# GS_V2.net
KiCad netlist of a schematic drawn in Altium Designer
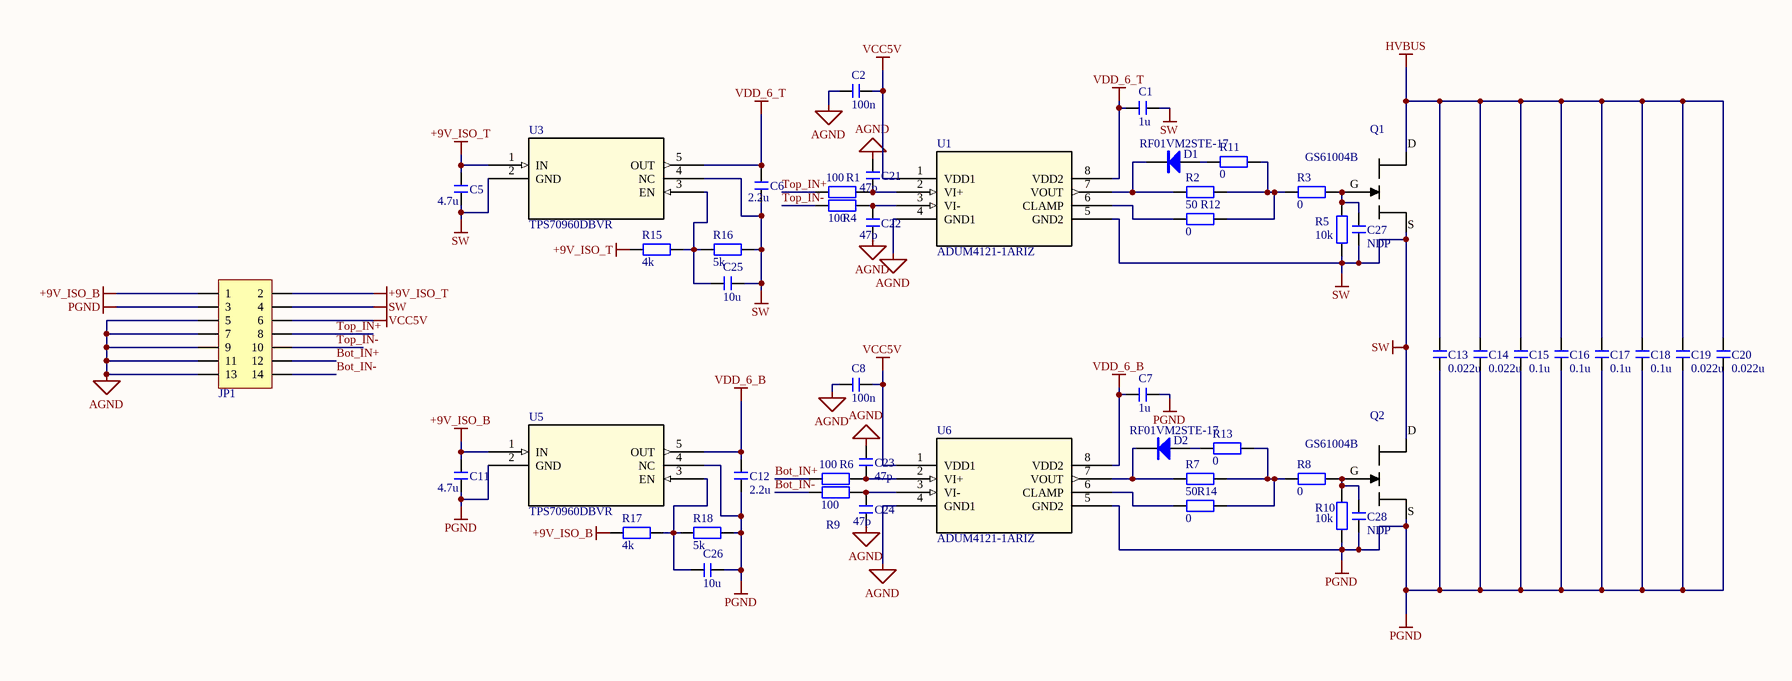
[diagram p0: GS_V2.SchDoc]

(export (version "E")
  (design (tool "Eeschema 10.0.6"))
  (components
    (comp (ref "C1")
      (value "1u")
      (footprint "C 0603_L")
      (description "无极性贴片电容")
      (fields (field (name "版权归属") "源创客"))
      (libsource (lib "3.1   - 电阻-电容-电感") (part "C"))
    )
    (comp (ref "C2")
      (value "100n")
      (footprint "C 0603_L")
      (description "无极性贴片电容")
      (fields (field (name "版权归属") "源创客"))
      (libsource (lib "3.1   - 电阻-电容-电感") (part "C"))
    )
    (comp (ref "C5")
      (value "4.7u")
      (footprint "C 0603_L")
      (description "无极性贴片电容")
      (fields (field (name "版权归属") "源创客"))
      (libsource (lib "3.1   - 电阻-电容-电感") (part "C"))
    )
    (comp (ref "C6")
      (value "2.2u")
      (footprint "C 0603_L")
      (description "无极性贴片电容")
      (fields (field (name "版权归属") "源创客"))
      (libsource (lib "3.1   - 电阻-电容-电感") (part "C"))
    )
    (comp (ref "C7")
      (value "1u")
      (footprint "C 0603_L")
      (description "无极性贴片电容")
      (fields (field (name "版权归属") "源创客"))
      (libsource (lib "3.1   - 电阻-电容-电感") (part "C"))
    )
    (comp (ref "C8")
      (value "100n")
      (footprint "C 0603_L")
      (description "无极性贴片电容")
      (fields (field (name "版权归属") "源创客"))
      (libsource (lib "3.1   - 电阻-电容-电感") (part "C"))
    )
    (comp (ref "C11")
      (value "4.7u")
      (footprint "C 0603_L")
      (description "无极性贴片电容")
      (fields (field (name "版权归属") "源创客"))
      (libsource (lib "3.1   - 电阻-电容-电感") (part "C"))
    )
    (comp (ref "C12")
      (value "2.2u")
      (footprint "C 0603_L")
      (description "无极性贴片电容")
      (fields (field (name "版权归属") "源创客"))
      (libsource (lib "3.1   - 电阻-电容-电感") (part "C"))
    )
    (comp (ref "C13")
      (value "0.022u")
      (footprint "C 0805_L")
      (description "无极性贴片电容")
      (fields (field (name "版权归属") "源创客"))
      (libsource (lib "3.1   - 电阻-电容-电感") (part "C"))
    )
    (comp (ref "C14")
      (value "0.022u")
      (footprint "C 0805_L")
      (description "无极性贴片电容")
      (fields (field (name "版权归属") "源创客"))
      (libsource (lib "3.1   - 电阻-电容-电感") (part "C"))
    )
    (comp (ref "C15")
      (value "0.1u")
      (footprint "C 0805_L")
      (description "无极性贴片电容")
      (fields (field (name "版权归属") "源创客"))
      (libsource (lib "3.1   - 电阻-电容-电感") (part "C"))
    )
    (comp (ref "C16")
      (value "0.1u")
      (footprint "C 0805_L")
      (description "无极性贴片电容")
      (fields (field (name "版权归属") "源创客"))
      (libsource (lib "3.1   - 电阻-电容-电感") (part "C"))
    )
    (comp (ref "C17")
      (value "0.1u")
      (footprint "C 0805_L")
      (description "无极性贴片电容")
      (fields (field (name "版权归属") "源创客"))
      (libsource (lib "3.1   - 电阻-电容-电感") (part "C"))
    )
    (comp (ref "C18")
      (value "0.1u")
      (footprint "C 0805_L")
      (description "无极性贴片电容")
      (fields (field (name "版权归属") "源创客"))
      (libsource (lib "3.1   - 电阻-电容-电感") (part "C"))
    )
    (comp (ref "C19")
      (value "0.022u")
      (footprint "C 0805_L")
      (description "无极性贴片电容")
      (fields (field (name "版权归属") "源创客"))
      (libsource (lib "3.1   - 电阻-电容-电感") (part "C"))
    )
    (comp (ref "C20")
      (value "0.022u")
      (footprint "C 0805_L")
      (description "无极性贴片电容")
      (fields (field (name "版权归属") "源创客"))
      (libsource (lib "3.1   - 电阻-电容-电感") (part "C"))
    )
    (comp (ref "C21")
      (value "47p")
      (footprint "C 0603_L")
      (description "无极性贴片电容")
      (fields (field (name "版权归属") "源创客"))
      (libsource (lib "3.1   - 电阻-电容-电感") (part "C"))
    )
    (comp (ref "C22")
      (value "47p")
      (footprint "C 0603_L")
      (description "无极性贴片电容")
      (fields (field (name "版权归属") "源创客"))
      (libsource (lib "3.1   - 电阻-电容-电感") (part "C"))
    )
    (comp (ref "C23")
      (value "47p")
      (footprint "C 0603_L")
      (description "无极性贴片电容")
      (fields (field (name "版权归属") "源创客"))
      (libsource (lib "3.1   - 电阻-电容-电感") (part "C"))
    )
    (comp (ref "C24")
      (value "47p")
      (footprint "C 0603_L")
      (description "无极性贴片电容")
      (fields (field (name "版权归属") "源创客"))
      (libsource (lib "3.1   - 电阻-电容-电感") (part "C"))
    )
    (comp (ref "C25")
      (value "10u")
      (footprint "C 0603_L")
      (description "无极性贴片电容")
      (fields (field (name "版权归属") "源创客"))
      (libsource (lib "3.1   - 电阻-电容-电感") (part "C"))
    )
    (comp (ref "C26")
      (value "10u")
      (footprint "C 0603_L")
      (description "无极性贴片电容")
      (fields (field (name "版权归属") "源创客"))
      (libsource (lib "3.1   - 电阻-电容-电感") (part "C"))
    )
    (comp (ref "C27")
      (value "NDP")
      (footprint "C 0603_L")
      (description "无极性贴片电容")
      (fields (field (name "版权归属") "源创客"))
      (libsource (lib "3.1   - 电阻-电容-电感") (part "C"))
    )
    (comp (ref "C28")
      (value "NDP")
      (footprint "C 0603_L")
      (description "无极性贴片电容")
      (fields (field (name "版权归属") "源创客"))
      (libsource (lib "3.1   - 电阻-电容-电感") (part "C"))
    )
    (comp (ref "D1")
      (value "RF01VM2STE-17")
      (footprint "SOD-323")
      (description "肖特基二极管")
      (fields (field (name "版权归属") "源创客"))
      (libsource (lib "8.1   - 二极管-整流桥") (part "1N5819"))
    )
    (comp (ref "D2")
      (value "RF01VM2STE-17")
      (footprint "SOD-323")
      (description "肖特基二极管")
      (fields (field (name "版权归属") "源创客"))
      (libsource (lib "8.1   - 二极管-整流桥") (part "1N5819"))
    )
    (comp (ref "JP1")
      (value "Header 2X7")
      (footprint "HDR2.54-WI-2x7P")
      (description "7*2P接插件")
      (fields (field (name "版权归属") "源创客"))
      (libsource (lib "4.6   - 接插件-脚距2.54") (part "Header 7X2"))
    )
    (comp (ref "Q1")
      (value "GS61004B")
      (footprint "GS61004B")
      (description "GAN TRANS E-MODE 100V")
      (libsource (lib "GANSYS_ALTIUM_SYMBOL_20220525") (part "GS61004B"))
    )
    (comp (ref "Q2")
      (value "GS61004B")
      (footprint "GS61004B")
      (description "GAN TRANS E-MODE 100V")
      (libsource (lib "GANSYS_ALTIUM_SYMBOL_20220525") (part "GS61004B"))
    )
    (comp (ref "R1")
      (value "100")
      (footprint "R 0603_L")
      (description "贴片电阻")
      (fields (field (name "版权归属") "源创客"))
      (libsource (lib "3.1   - 电阻-电容-电感") (part "R"))
    )
    (comp (ref "R2")
      (value "50")
      (footprint "R 0603_L")
      (description "贴片电阻")
      (fields (field (name "版权归属") "源创客"))
      (libsource (lib "3.1   - 电阻-电容-电感") (part "R"))
    )
    (comp (ref "R3")
      (value "0")
      (footprint "R 0603_L")
      (description "贴片电阻")
      (fields (field (name "版权归属") "源创客"))
      (libsource (lib "3.1   - 电阻-电容-电感") (part "R"))
    )
    (comp (ref "R4")
      (value "100")
      (footprint "R 0603_L")
      (description "贴片电阻")
      (fields (field (name "版权归属") "源创客"))
      (libsource (lib "3.1   - 电阻-电容-电感") (part "R"))
    )
    (comp (ref "R5")
      (value "10k")
      (footprint "R 0603_L")
      (description "贴片电阻")
      (fields (field (name "版权归属") "源创客"))
      (libsource (lib "3.1   - 电阻-电容-电感") (part "R"))
    )
    (comp (ref "R6")
      (value "100")
      (footprint "R 0603_L")
      (description "贴片电阻")
      (fields (field (name "版权归属") "源创客"))
      (libsource (lib "3.1   - 电阻-电容-电感") (part "R"))
    )
    (comp (ref "R7")
      (value "50")
      (footprint "R 0603_L")
      (description "贴片电阻")
      (fields (field (name "版权归属") "源创客"))
      (libsource (lib "3.1   - 电阻-电容-电感") (part "R"))
    )
    (comp (ref "R8")
      (value "0")
      (footprint "R 0603_L")
      (description "贴片电阻")
      (fields (field (name "版权归属") "源创客"))
      (libsource (lib "3.1   - 电阻-电容-电感") (part "R"))
    )
    (comp (ref "R9")
      (value "100")
      (footprint "R 0603_L")
      (description "贴片电阻")
      (fields (field (name "版权归属") "源创客"))
      (libsource (lib "3.1   - 电阻-电容-电感") (part "R"))
    )
    (comp (ref "R10")
      (value "10k")
      (footprint "R 0603_L")
      (description "贴片电阻")
      (fields (field (name "版权归属") "源创客"))
      (libsource (lib "3.1   - 电阻-电容-电感") (part "R"))
    )
    (comp (ref "R11")
      (value "0")
      (footprint "R 0603_L")
      (description "贴片电阻")
      (fields (field (name "版权归属") "源创客"))
      (libsource (lib "3.1   - 电阻-电容-电感") (part "R"))
    )
    (comp (ref "R12")
      (value "0")
      (footprint "R 0603_L")
      (description "贴片电阻")
      (fields (field (name "版权归属") "源创客"))
      (libsource (lib "3.1   - 电阻-电容-电感") (part "R"))
    )
    (comp (ref "R13")
      (value "0")
      (footprint "R 0603_L")
      (description "贴片电阻")
      (fields (field (name "版权归属") "源创客"))
      (libsource (lib "3.1   - 电阻-电容-电感") (part "R"))
    )
    (comp (ref "R14")
      (value "0")
      (footprint "R 0603_L")
      (description "贴片电阻")
      (fields (field (name "版权归属") "源创客"))
      (libsource (lib "3.1   - 电阻-电容-电感") (part "R"))
    )
    (comp (ref "R15")
      (value "4k")
      (footprint "R 0603_L")
      (description "贴片电阻")
      (fields (field (name "版权归属") "源创客"))
      (libsource (lib "3.1   - 电阻-电容-电感") (part "R"))
    )
    (comp (ref "R16")
      (value "5k")
      (footprint "R 0603_L")
      (description "贴片电阻")
      (fields (field (name "版权归属") "源创客"))
      (libsource (lib "3.1   - 电阻-电容-电感") (part "R"))
    )
    (comp (ref "R17")
      (value "4k")
      (footprint "R 0603_L")
      (description "贴片电阻")
      (fields (field (name "版权归属") "源创客"))
      (libsource (lib "3.1   - 电阻-电容-电感") (part "R"))
    )
    (comp (ref "R18")
      (value "5k")
      (footprint "R 0603_L")
      (description "贴片电阻")
      (fields (field (name "版权归属") "源创客"))
      (libsource (lib "3.1   - 电阻-电容-电感") (part "R"))
    )
    (comp (ref "U1")
      (value "ADUM4121-1ARIZ")
      (footprint "RI-8-1_ADI")
      (description "No Description Available")
      (libsource (lib "ADUM4121-1ARIZ") (part "ADUM4121-1ARIZ"))
    )
    (comp (ref "U3")
      (value "TPS70960DBVR")
      (footprint "DBV5_TEX")
      (description "No Description Available")
      (libsource (lib "TPS70960DBVR") (part "TPS70960DBVR"))
    )
    (comp (ref "U5")
      (value "TPS70960DBVR")
      (footprint "DBV5_TEX")
      (description "No Description Available")
      (libsource (lib "TPS70960DBVR") (part "TPS70960DBVR"))
    )
    (comp (ref "U6")
      (value "ADUM4121-1ARIZ")
      (footprint "RI-8-1_ADI")
      (description "No Description Available")
      (libsource (lib "ADUM4121-1ARIZ") (part "ADUM4121-1ARIZ"))
    )
  )
  (nets
    (net (code "1") (name "+9V_ISO_B") (class "Default")
      (node (ref "C11") (pin "2") (pinfunction "2_2") (pintype "passive"))
      (node (ref "JP1") (pin "1") (pinfunction "1_1") (pintype "passive"))
      (node (ref "R17") (pin "2") (pinfunction "2_2") (pintype "passive"))
      (node (ref "U5") (pin "1") (pinfunction "IN_1") (pintype "input"))
    )
    (net (code "2") (name "+9V_ISO_T") (class "Default")
      (node (ref "C5") (pin "2") (pinfunction "2_2") (pintype "passive"))
      (node (ref "JP1") (pin "2") (pinfunction "2_2") (pintype "passive"))
      (node (ref "R15") (pin "2") (pinfunction "2_2") (pintype "passive"))
      (node (ref "U3") (pin "1") (pinfunction "IN_1") (pintype "input"))
    )
    (net (code "3") (name "/Bot_IN+") (class "Default")
      (node (ref "JP1") (pin "12") (pinfunction "12_12") (pintype "passive"))
      (node (ref "R6") (pin "1") (pinfunction "1_1") (pintype "passive"))
    )
    (net (code "4") (name "/Bot_IN-") (class "Default")
      (node (ref "JP1") (pin "14") (pinfunction "14_14") (pintype "passive"))
      (node (ref "R9") (pin "1") (pinfunction "1_1") (pintype "passive"))
    )
    (net (code "5") (name "/Top_IN+") (class "Default")
      (node (ref "JP1") (pin "8") (pinfunction "8_8") (pintype "passive"))
      (node (ref "R1") (pin "1") (pinfunction "1_1") (pintype "passive"))
    )
    (net (code "6") (name "/Top_IN-") (class "Default")
      (node (ref "JP1") (pin "10") (pinfunction "10_10") (pintype "passive"))
      (node (ref "R4") (pin "1") (pinfunction "1_1") (pintype "passive"))
    )
    (net (code "7") (name "AGND") (class "Default")
      (node (ref "C2") (pin "2") (pinfunction "2_2") (pintype "passive"))
      (node (ref "C21") (pin "2") (pinfunction "2_2") (pintype "passive"))
      (node (ref "C22") (pin "1") (pinfunction "1_1") (pintype "passive"))
      (node (ref "C23") (pin "1") (pinfunction "1_1") (pintype "passive"))
      (node (ref "C24") (pin "1") (pinfunction "1_1") (pintype "passive"))
      (node (ref "C8") (pin "2") (pinfunction "2_2") (pintype "passive"))
      (node (ref "JP1") (pin "11") (pinfunction "11_11") (pintype "passive"))
      (node (ref "JP1") (pin "13") (pinfunction "13_13") (pintype "passive"))
      (node (ref "JP1") (pin "5") (pinfunction "5_5") (pintype "passive"))
      (node (ref "JP1") (pin "7") (pinfunction "7_7") (pintype "passive"))
      (node (ref "JP1") (pin "9") (pinfunction "9_9") (pintype "passive"))
      (node (ref "U1") (pin "4") (pinfunction "GND1_4") (pintype "power_in"))
      (node (ref "U6") (pin "4") (pinfunction "GND1_4") (pintype "power_in"))
    )
    (net (code "8") (name "HVBUS") (class "Default")
      (node (ref "C13") (pin "2") (pinfunction "2_2") (pintype "passive"))
      (node (ref "C14") (pin "2") (pinfunction "2_2") (pintype "passive"))
      (node (ref "C15") (pin "2") (pinfunction "2_2") (pintype "passive"))
      (node (ref "C16") (pin "2") (pinfunction "2_2") (pintype "passive"))
      (node (ref "C17") (pin "2") (pinfunction "2_2") (pintype "passive"))
      (node (ref "C18") (pin "2") (pinfunction "2_2") (pintype "passive"))
      (node (ref "C19") (pin "2") (pinfunction "2_2") (pintype "passive"))
      (node (ref "C20") (pin "2") (pinfunction "2_2") (pintype "passive"))
      (node (ref "Q1") (pin "D") (pinfunction "D_D") (pintype "passive"))
    )
    (net (code "9") (name "Net-(C27-Pad1)") (class "Default")
      (node (ref "C27") (pin "1") (pinfunction "1_1") (pintype "passive"))
      (node (ref "Q1") (pin "G") (pinfunction "G_G") (pintype "passive"))
      (node (ref "R3") (pin "2") (pinfunction "2_2") (pintype "passive"))
      (node (ref "R5") (pin "2") (pinfunction "2_2") (pintype "passive"))
    )
    (net (code "10") (name "Net-(C28-Pad1)") (class "Default")
      (node (ref "C28") (pin "1") (pinfunction "1_1") (pintype "passive"))
      (node (ref "Q2") (pin "G") (pinfunction "G_G") (pintype "passive"))
      (node (ref "R10") (pin "2") (pinfunction "2_2") (pintype "passive"))
      (node (ref "R8") (pin "2") (pinfunction "2_2") (pintype "passive"))
    )
    (net (code "11") (name "Net-(D1-A)") (class "Default")
      (node (ref "D1") (pin "1") (pinfunction "A_1") (pintype "passive"))
      (node (ref "R11") (pin "1") (pinfunction "1_1") (pintype "passive"))
    )
    (net (code "12") (name "Net-(D1-K)") (class "Default")
      (node (ref "D1") (pin "2") (pinfunction "K_2") (pintype "passive"))
      (node (ref "R2") (pin "1") (pinfunction "1_1") (pintype "passive"))
      (node (ref "U1") (pin "7") (pinfunction "VOUT_7") (pintype "output"))
    )
    (net (code "13") (name "Net-(D2-A)") (class "Default")
      (node (ref "D2") (pin "1") (pinfunction "A_1") (pintype "passive"))
      (node (ref "R13") (pin "1") (pinfunction "1_1") (pintype "passive"))
    )
    (net (code "14") (name "Net-(D2-K)") (class "Default")
      (node (ref "D2") (pin "2") (pinfunction "K_2") (pintype "passive"))
      (node (ref "R7") (pin "1") (pinfunction "1_1") (pintype "passive"))
      (node (ref "U6") (pin "7") (pinfunction "VOUT_7") (pintype "output"))
    )
    (net (code "15") (name "Net-(R11-Pad2)") (class "Default")
      (node (ref "R11") (pin "2") (pinfunction "2_2") (pintype "passive"))
      (node (ref "R12") (pin "2") (pinfunction "2_2") (pintype "passive"))
      (node (ref "R2") (pin "2") (pinfunction "2_2") (pintype "passive"))
      (node (ref "R3") (pin "1") (pinfunction "1_1") (pintype "passive"))
    )
    (net (code "16") (name "Net-(R13-Pad2)") (class "Default")
      (node (ref "R13") (pin "2") (pinfunction "2_2") (pintype "passive"))
      (node (ref "R14") (pin "2") (pinfunction "2_2") (pintype "passive"))
      (node (ref "R7") (pin "2") (pinfunction "2_2") (pintype "passive"))
      (node (ref "R8") (pin "1") (pinfunction "1_1") (pintype "passive"))
    )
    (net (code "17") (name "Net-(U1-CLAMP)") (class "Default")
      (node (ref "R12") (pin "1") (pinfunction "1_1") (pintype "passive"))
      (node (ref "U1") (pin "6") (pinfunction "CLAMP_6") (pintype "passive"))
    )
    (net (code "18") (name "Net-(U1-VI+)") (class "Default")
      (node (ref "C21") (pin "1") (pinfunction "1_1") (pintype "passive"))
      (node (ref "R1") (pin "2") (pinfunction "2_2") (pintype "passive"))
      (node (ref "U1") (pin "2") (pinfunction "VI+_2") (pintype "input"))
    )
    (net (code "19") (name "Net-(U1-VI-)") (class "Default")
      (node (ref "C22") (pin "2") (pinfunction "2_2") (pintype "passive"))
      (node (ref "R4") (pin "2") (pinfunction "2_2") (pintype "passive"))
      (node (ref "U1") (pin "3") (pinfunction "VI-_3") (pintype "input"))
    )
    (net (code "20") (name "Net-(U3-EN)") (class "Default")
      (node (ref "C25") (pin "2") (pinfunction "2_2") (pintype "passive"))
      (node (ref "R15") (pin "1") (pinfunction "1_1") (pintype "passive"))
      (node (ref "R16") (pin "2") (pinfunction "2_2") (pintype "passive"))
      (node (ref "U3") (pin "3") (pinfunction "EN_3") (pintype "input"))
    )
    (net (code "21") (name "Net-(U5-EN)") (class "Default")
      (node (ref "C26") (pin "2") (pinfunction "2_2") (pintype "passive"))
      (node (ref "R17") (pin "1") (pinfunction "1_1") (pintype "passive"))
      (node (ref "R18") (pin "2") (pinfunction "2_2") (pintype "passive"))
      (node (ref "U5") (pin "3") (pinfunction "EN_3") (pintype "input"))
    )
    (net (code "22") (name "Net-(U6-CLAMP)") (class "Default")
      (node (ref "R14") (pin "1") (pinfunction "1_1") (pintype "passive"))
      (node (ref "U6") (pin "6") (pinfunction "CLAMP_6") (pintype "passive"))
    )
    (net (code "23") (name "Net-(U6-VI+)") (class "Default")
      (node (ref "C23") (pin "2") (pinfunction "2_2") (pintype "passive"))
      (node (ref "R6") (pin "2") (pinfunction "2_2") (pintype "passive"))
      (node (ref "U6") (pin "2") (pinfunction "VI+_2") (pintype "input"))
    )
    (net (code "24") (name "Net-(U6-VI-)") (class "Default")
      (node (ref "C24") (pin "2") (pinfunction "2_2") (pintype "passive"))
      (node (ref "R9") (pin "2") (pinfunction "2_2") (pintype "passive"))
      (node (ref "U6") (pin "3") (pinfunction "VI-_3") (pintype "input"))
    )
    (net (code "25") (name "PGND") (class "Default")
      (node (ref "C11") (pin "1") (pinfunction "1_1") (pintype "passive"))
      (node (ref "C12") (pin "1") (pinfunction "1_1") (pintype "passive"))
      (node (ref "C13") (pin "1") (pinfunction "1_1") (pintype "passive"))
      (node (ref "C14") (pin "1") (pinfunction "1_1") (pintype "passive"))
      (node (ref "C15") (pin "1") (pinfunction "1_1") (pintype "passive"))
      (node (ref "C16") (pin "1") (pinfunction "1_1") (pintype "passive"))
      (node (ref "C17") (pin "1") (pinfunction "1_1") (pintype "passive"))
      (node (ref "C18") (pin "1") (pinfunction "1_1") (pintype "passive"))
      (node (ref "C19") (pin "1") (pinfunction "1_1") (pintype "passive"))
      (node (ref "C20") (pin "1") (pinfunction "1_1") (pintype "passive"))
      (node (ref "C26") (pin "1") (pinfunction "1_1") (pintype "passive"))
      (node (ref "C28") (pin "2") (pinfunction "2_2") (pintype "passive"))
      (node (ref "C7") (pin "2") (pinfunction "2_2") (pintype "passive"))
      (node (ref "JP1") (pin "3") (pinfunction "3_3") (pintype "passive"))
      (node (ref "Q2") (pin "S") (pinfunction "S_S") (pintype "passive"))
      (node (ref "R10") (pin "1") (pinfunction "1_1") (pintype "passive"))
      (node (ref "R18") (pin "1") (pinfunction "1_1") (pintype "passive"))
      (node (ref "U5") (pin "2") (pinfunction "GND_2") (pintype "power_in"))
      (node (ref "U5") (pin "4") (pinfunction "NC_4") (pintype "passive"))
      (node (ref "U6") (pin "5") (pinfunction "GND2_5") (pintype "power_in"))
    )
    (net (code "26") (name "SW") (class "Default")
      (node (ref "C1") (pin "2") (pinfunction "2_2") (pintype "passive"))
      (node (ref "C25") (pin "1") (pinfunction "1_1") (pintype "passive"))
      (node (ref "C27") (pin "2") (pinfunction "2_2") (pintype "passive"))
      (node (ref "C5") (pin "1") (pinfunction "1_1") (pintype "passive"))
      (node (ref "C6") (pin "1") (pinfunction "1_1") (pintype "passive"))
      (node (ref "JP1") (pin "4") (pinfunction "4_4") (pintype "passive"))
      (node (ref "Q1") (pin "S") (pinfunction "S_S") (pintype "passive"))
      (node (ref "Q2") (pin "D") (pinfunction "D_D") (pintype "passive"))
      (node (ref "R16") (pin "1") (pinfunction "1_1") (pintype "passive"))
      (node (ref "R5") (pin "1") (pinfunction "1_1") (pintype "passive"))
      (node (ref "U1") (pin "5") (pinfunction "GND2_5") (pintype "power_in"))
      (node (ref "U3") (pin "2") (pinfunction "GND_2") (pintype "power_in"))
      (node (ref "U3") (pin "4") (pinfunction "NC_4") (pintype "passive"))
    )
    (net (code "27") (name "VCC5V") (class "Default")
      (node (ref "C2") (pin "1") (pinfunction "1_1") (pintype "passive"))
      (node (ref "C8") (pin "1") (pinfunction "1_1") (pintype "passive"))
      (node (ref "JP1") (pin "6") (pinfunction "6_6") (pintype "passive"))
      (node (ref "U1") (pin "1") (pinfunction "VDD1_1") (pintype "power_in"))
      (node (ref "U6") (pin "1") (pinfunction "VDD1_1") (pintype "power_in"))
    )
    (net (code "28") (name "VDD_6_B") (class "Default")
      (node (ref "C12") (pin "2") (pinfunction "2_2") (pintype "passive"))
      (node (ref "C7") (pin "1") (pinfunction "1_1") (pintype "passive"))
      (node (ref "U5") (pin "5") (pinfunction "OUT_5") (pintype "output"))
      (node (ref "U6") (pin "8") (pinfunction "VDD2_8") (pintype "power_in"))
    )
    (net (code "29") (name "VDD_6_T") (class "Default")
      (node (ref "C1") (pin "1") (pinfunction "1_1") (pintype "passive"))
      (node (ref "C6") (pin "2") (pinfunction "2_2") (pintype "passive"))
      (node (ref "U1") (pin "8") (pinfunction "VDD2_8") (pintype "power_in"))
      (node (ref "U3") (pin "5") (pinfunction "OUT_5") (pintype "output"))
    )
  )
)
